# SignalReciever.net
KiCad netlist of a schematic drawn in Altium Designer
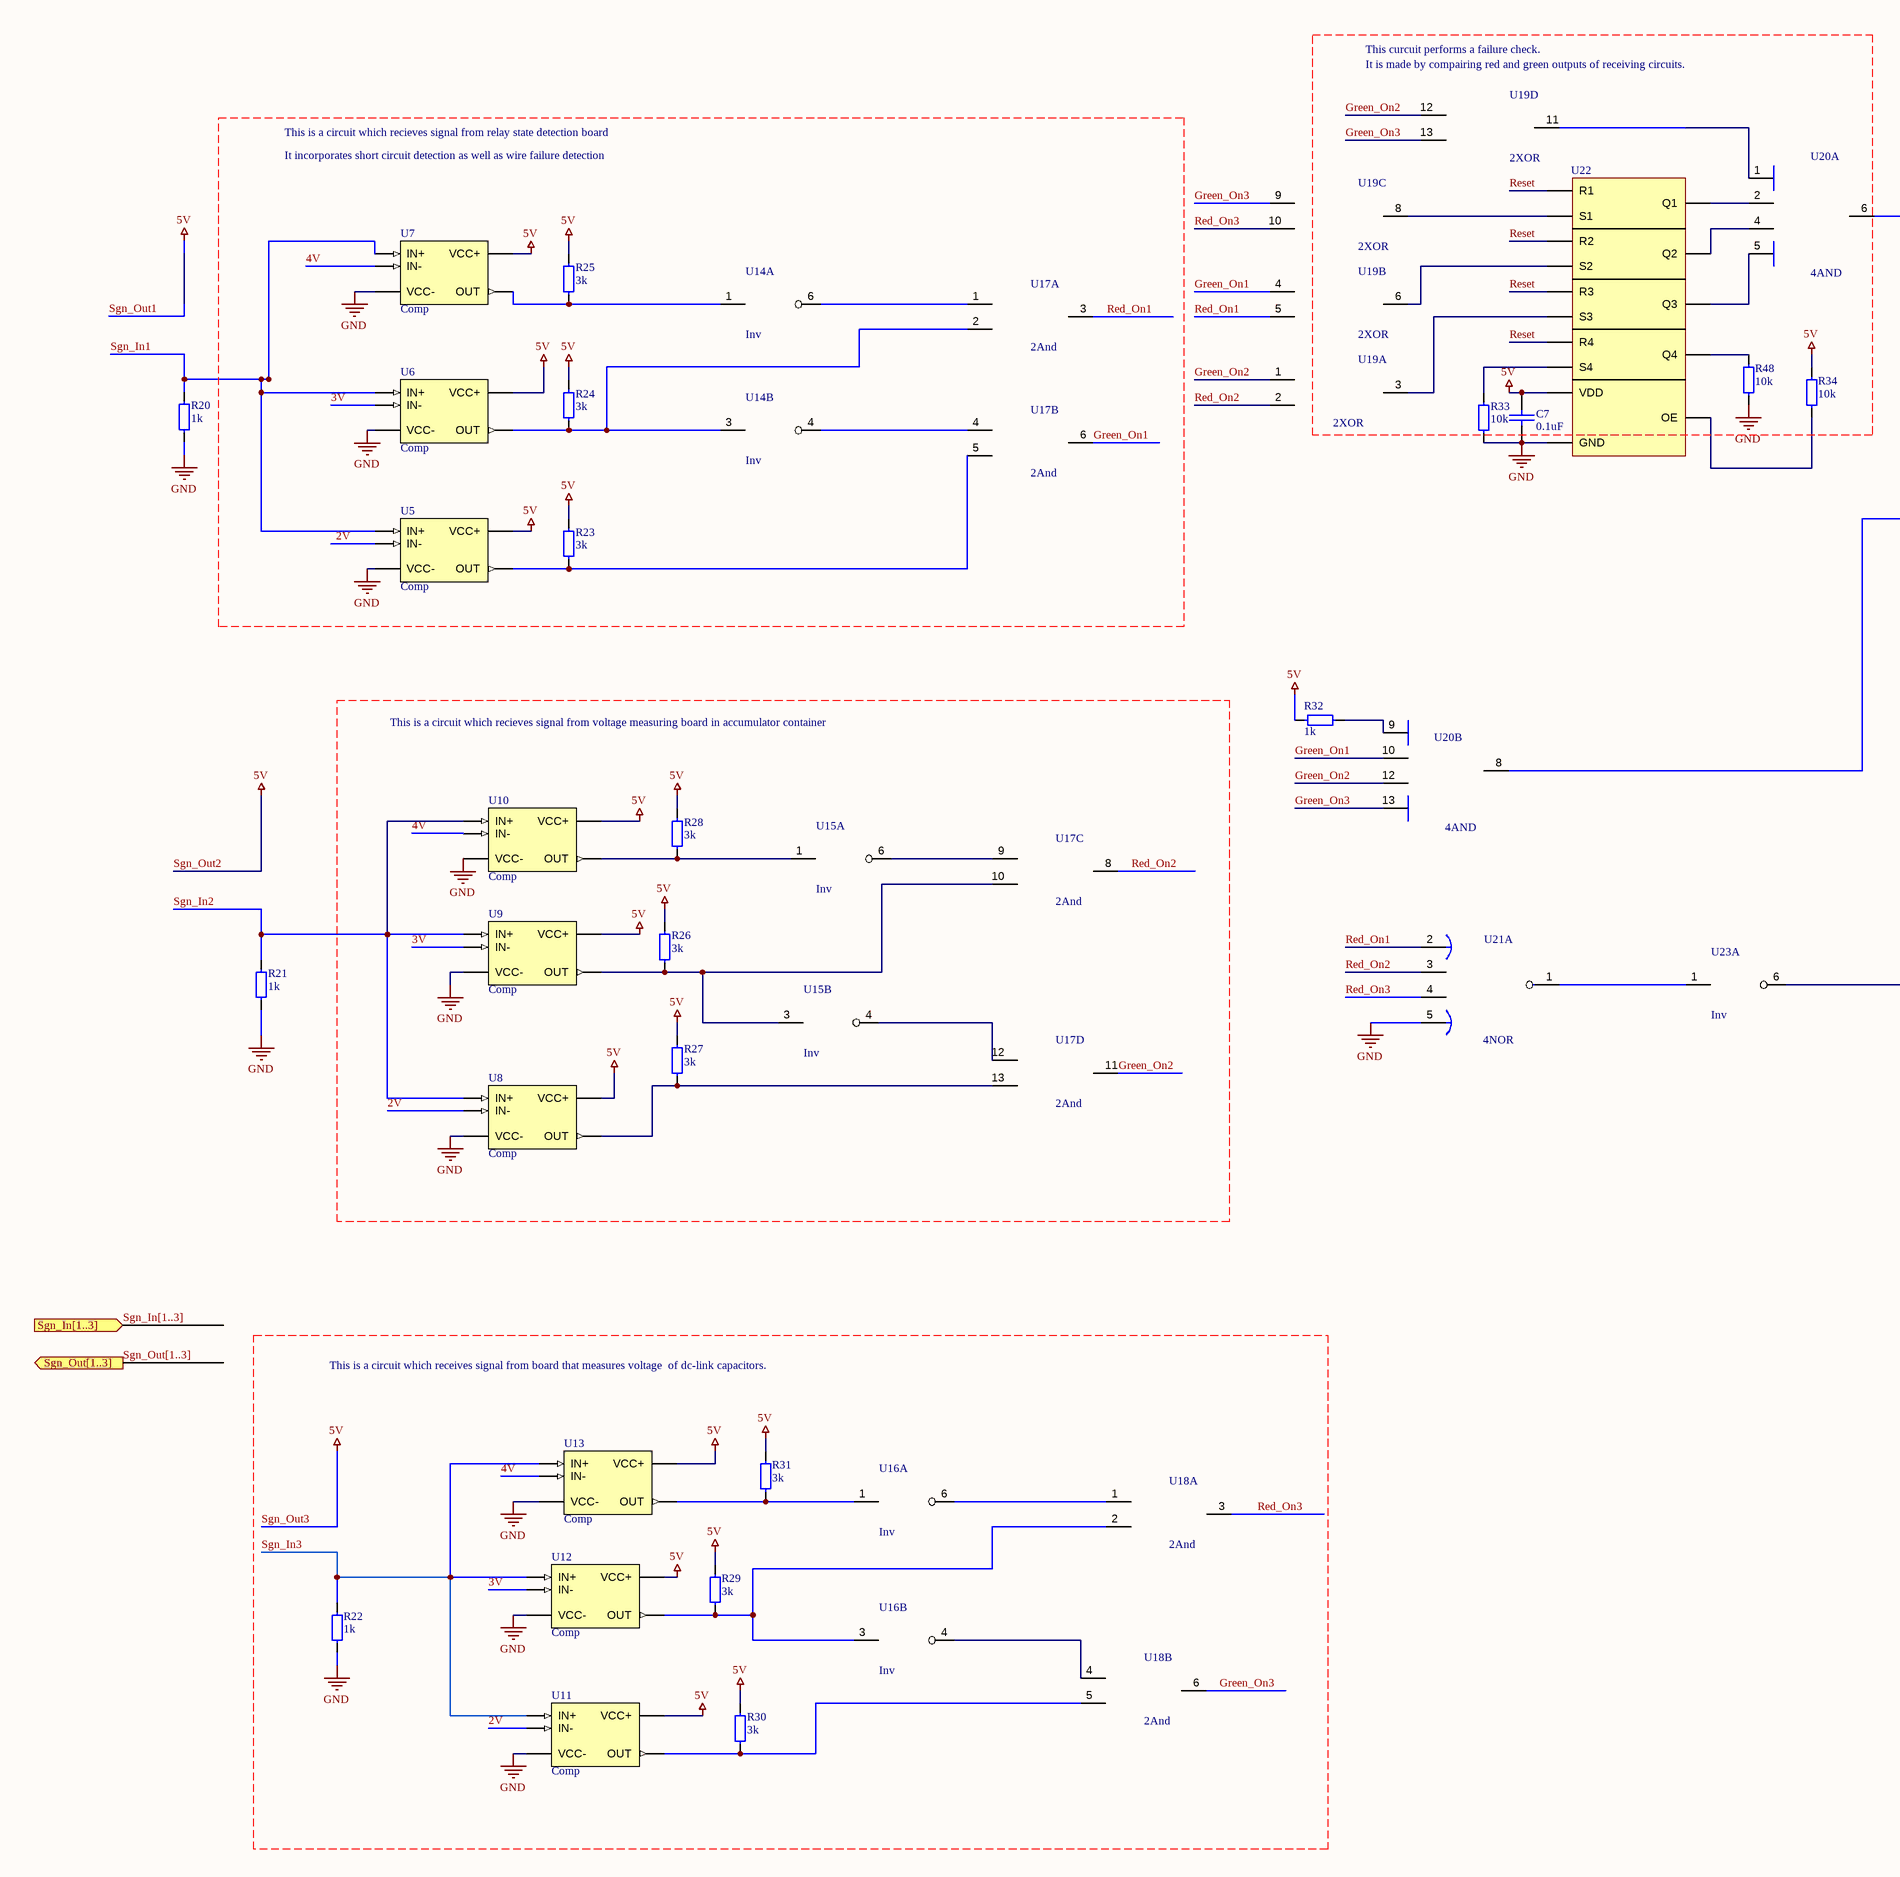
[diagram p0: SignalReciever.SchDoc, left]
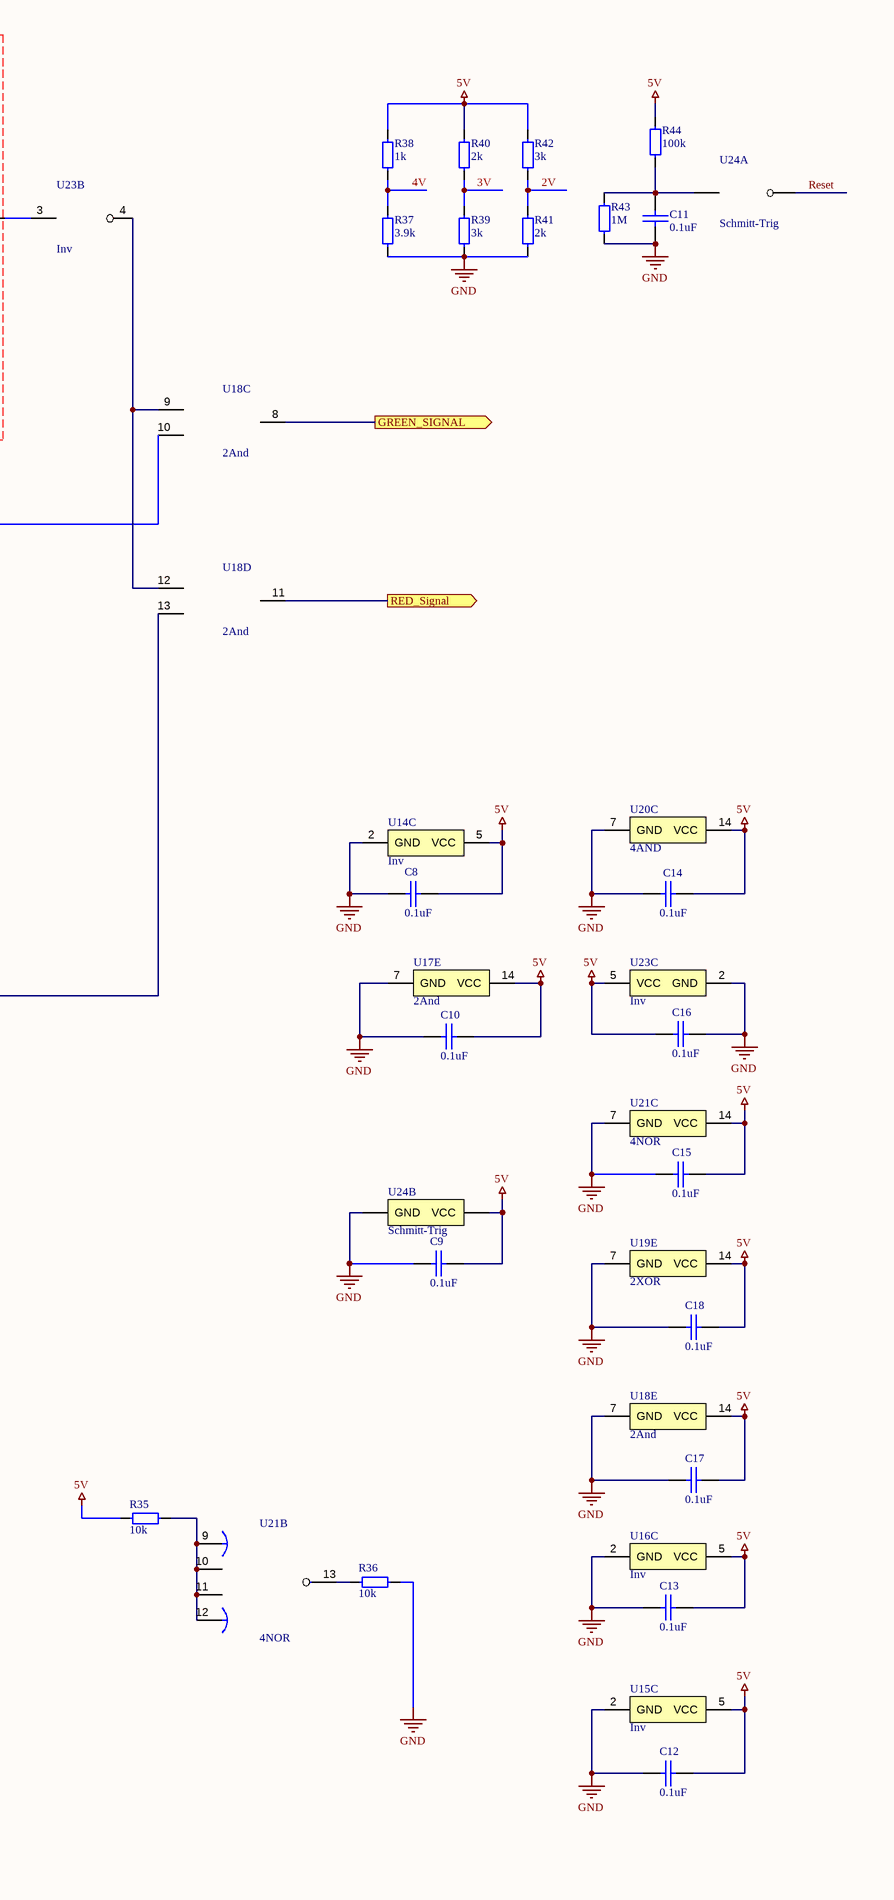
[diagram p1: SignalReciever.SchDoc, right]

(export (version "E")
  (design (tool "Eeschema 10.0.6"))
  (components
    (comp (ref "C7")
      (value "0.1uF")
      (footprint "0603 Capicator")
      (description "0.1uF X7R 16V 10% 0603")
      (fields
        (field (name "MANUFACTURER") "Murata Manufacturing")
        (field (name "PART NUMBER") "GRM188R71C104KA01D")
      )
      (libsource (lib "BRT_Components") (part "Cap 0.1uF (0603)"))
    )
    (comp (ref "C8")
      (value "0.1uF")
      (footprint "0603 Capicator")
      (description "0.1uF X7R 16V 10% 0603")
      (fields
        (field (name "MANUFACTURER") "Murata Manufacturing")
        (field (name "PART NUMBER") "GRM188R71C104KA01D")
      )
      (libsource (lib "BRT_Components") (part "Cap 0.1uF (0603)"))
    )
    (comp (ref "C9")
      (value "0.1uF")
      (footprint "0603 Capicator")
      (description "0.1uF X7R 16V 10% 0603")
      (fields
        (field (name "MANUFACTURER") "Murata Manufacturing")
        (field (name "PART NUMBER") "GRM188R71C104KA01D")
      )
      (libsource (lib "BRT_Components") (part "Cap 0.1uF (0603)"))
    )
    (comp (ref "C10")
      (value "0.1uF")
      (footprint "0603 Capicator")
      (description "0.1uF X7R 16V 10% 0603")
      (fields
        (field (name "MANUFACTURER") "Murata Manufacturing")
        (field (name "PART NUMBER") "GRM188R71C104KA01D")
      )
      (libsource (lib "BRT_Components") (part "Cap 0.1uF (0603)"))
    )
    (comp (ref "C11")
      (value "0.1uF")
      (footprint "0603 Capicator")
      (description "0.1uF X7R 16V 10% 0603")
      (fields
        (field (name "MANUFACTURER") "Murata Manufacturing")
        (field (name "PART NUMBER") "GRM188R71C104KA01D")
      )
      (libsource (lib "BRT_Components") (part "Cap 0.1uF (0603)"))
    )
    (comp (ref "C12")
      (value "0.1uF")
      (footprint "0603 Capicator")
      (description "0.1uF X7R 16V 10% 0603")
      (fields
        (field (name "MANUFACTURER") "Murata Manufacturing")
        (field (name "PART NUMBER") "GRM188R71C104KA01D")
      )
      (libsource (lib "BRT_Components") (part "Cap 0.1uF (0603)"))
    )
    (comp (ref "C13")
      (value "0.1uF")
      (footprint "0603 Capicator")
      (description "0.1uF X7R 16V 10% 0603")
      (fields
        (field (name "MANUFACTURER") "Murata Manufacturing")
        (field (name "PART NUMBER") "GRM188R71C104KA01D")
      )
      (libsource (lib "BRT_Components") (part "Cap 0.1uF (0603)"))
    )
    (comp (ref "C14")
      (value "0.1uF")
      (footprint "0603 Capicator")
      (description "0.1uF X7R 16V 10% 0603")
      (fields
        (field (name "MANUFACTURER") "Murata Manufacturing")
        (field (name "PART NUMBER") "GRM188R71C104KA01D")
      )
      (libsource (lib "BRT_Components") (part "Cap 0.1uF (0603)"))
    )
    (comp (ref "C15")
      (value "0.1uF")
      (footprint "0603 Capicator")
      (description "0.1uF X7R 16V 10% 0603")
      (fields
        (field (name "MANUFACTURER") "Murata Manufacturing")
        (field (name "PART NUMBER") "GRM188R71C104KA01D")
      )
      (libsource (lib "BRT_Components") (part "Cap 0.1uF (0603)"))
    )
    (comp (ref "C16")
      (value "0.1uF")
      (footprint "0603 Capicator")
      (description "0.1uF X7R 16V 10% 0603")
      (fields
        (field (name "MANUFACTURER") "Murata Manufacturing")
        (field (name "PART NUMBER") "GRM188R71C104KA01D")
      )
      (libsource (lib "BRT_Components") (part "Cap 0.1uF (0603)"))
    )
    (comp (ref "C17")
      (value "0.1uF")
      (footprint "0603 Capicator")
      (description "0.1uF X7R 16V 10% 0603")
      (fields
        (field (name "MANUFACTURER") "Murata Manufacturing")
        (field (name "PART NUMBER") "GRM188R71C104KA01D")
      )
      (libsource (lib "BRT_Components") (part "Cap 0.1uF (0603)"))
    )
    (comp (ref "C18")
      (value "0.1uF")
      (footprint "0603 Capicator")
      (description "0.1uF X7R 16V 10% 0603")
      (fields
        (field (name "MANUFACTURER") "Murata Manufacturing")
        (field (name "PART NUMBER") "GRM188R71C104KA01D")
      )
      (libsource (lib "BRT_Components") (part "Cap 0.1uF (0603)"))
    )
    (comp (ref "R20")
      (value "1k")
      (footprint "0603 Resistor")
      (description "0.1W 0603 1k, 1%")
      (fields (field (name "PART NUMBER") "RC0603FR-071KL") (field (name "MANUFACTURER") "Taiwan"))
      (libsource (lib "BRT_Components") (part "Res 1k (0603)"))
    )
    (comp (ref "R21")
      (value "1k")
      (footprint "0603 Resistor")
      (description "0.1W 0603 1k, 1%")
      (fields (field (name "PART NUMBER") "RC0603FR-071KL") (field (name "MANUFACTURER") "Taiwan"))
      (libsource (lib "BRT_Components") (part "Res 1k (0603)"))
    )
    (comp (ref "R22")
      (value "1k")
      (footprint "0603 Resistor")
      (description "0.1W 0603 1k, 1%")
      (fields (field (name "PART NUMBER") "RC0603FR-071KL") (field (name "MANUFACTURER") "Taiwan"))
      (libsource (lib "BRT_Components") (part "Res 1k (0603)"))
    )
    (comp (ref "R23")
      (value "3k")
      (footprint "0603 Resistor")
      (description "0.1W 0603 3k, 1%")
      (fields (field (name "PART NUMBER") "RC0603FR-073KL") (field (name "MANUFACTURER") "Taiwan"))
      (libsource (lib "BRT_Components") (part "Res 3k (0603)"))
    )
    (comp (ref "R24")
      (value "3k")
      (footprint "0603 Resistor")
      (description "0.1W 0603 3k, 1%")
      (fields (field (name "PART NUMBER") "RC0603FR-073KL") (field (name "MANUFACTURER") "Taiwan"))
      (libsource (lib "BRT_Components") (part "Res 3k (0603)"))
    )
    (comp (ref "R25")
      (value "3k")
      (footprint "0603 Resistor")
      (description "0.1W 0603 3k, 1%")
      (fields (field (name "PART NUMBER") "RC0603FR-073KL") (field (name "MANUFACTURER") "Taiwan"))
      (libsource (lib "BRT_Components") (part "Res 3k (0603)"))
    )
    (comp (ref "R26")
      (value "3k")
      (footprint "0603 Resistor")
      (description "0.1W 0603 3k, 1%")
      (fields (field (name "PART NUMBER") "RC0603FR-073KL") (field (name "MANUFACTURER") "Taiwan"))
      (libsource (lib "BRT_Components") (part "Res 3k (0603)"))
    )
    (comp (ref "R27")
      (value "3k")
      (footprint "0603 Resistor")
      (description "0.1W 0603 3k, 1%")
      (fields (field (name "PART NUMBER") "RC0603FR-073KL") (field (name "MANUFACTURER") "Taiwan"))
      (libsource (lib "BRT_Components") (part "Res 3k (0603)"))
    )
    (comp (ref "R28")
      (value "3k")
      (footprint "0603 Resistor")
      (description "0.1W 0603 3k, 1%")
      (fields (field (name "PART NUMBER") "RC0603FR-073KL") (field (name "MANUFACTURER") "Taiwan"))
      (libsource (lib "BRT_Components") (part "Res 3k (0603)"))
    )
    (comp (ref "R29")
      (value "3k")
      (footprint "0603 Resistor")
      (description "0.1W 0603 3k, 1%")
      (fields (field (name "PART NUMBER") "RC0603FR-073KL") (field (name "MANUFACTURER") "Taiwan"))
      (libsource (lib "BRT_Components") (part "Res 3k (0603)"))
    )
    (comp (ref "R30")
      (value "3k")
      (footprint "0603 Resistor")
      (description "0.1W 0603 3k, 1%")
      (fields (field (name "PART NUMBER") "RC0603FR-073KL") (field (name "MANUFACTURER") "Taiwan"))
      (libsource (lib "BRT_Components") (part "Res 3k (0603)"))
    )
    (comp (ref "R31")
      (value "3k")
      (footprint "0603 Resistor")
      (description "0.1W 0603 3k, 1%")
      (fields (field (name "PART NUMBER") "RC0603FR-073KL") (field (name "MANUFACTURER") "Taiwan"))
      (libsource (lib "BRT_Components") (part "Res 3k (0603)"))
    )
    (comp (ref "R32")
      (value "1k")
      (footprint "0603 Resistor")
      (description "0.1W 0603 1k, 1%")
      (fields (field (name "PART NUMBER") "RC0603FR-071KL") (field (name "MANUFACTURER") "Taiwan"))
      (libsource (lib "BRT_Components") (part "Res 1k (0603)"))
    )
    (comp (ref "R33")
      (value "10k")
      (footprint "0603 Resistor")
      (description "0.1W 0603 10k, 1%")
      (fields (field (name "PART NUMBER") "RC0603FR-0710KL") (field (name "MANUFACTURER") "Taiwan"))
      (libsource (lib "BRT_Components") (part "Res 10k (0603)"))
    )
    (comp (ref "R34")
      (value "10k")
      (footprint "0603 Resistor")
      (description "0.1W 0603 10k, 1%")
      (fields (field (name "PART NUMBER") "RC0603FR-0710KL") (field (name "MANUFACTURER") "Taiwan"))
      (libsource (lib "BRT_Components") (part "Res 10k (0603)"))
    )
    (comp (ref "R35")
      (value "10k")
      (footprint "0603 Resistor")
      (description "0.1W 0603 10k, 1%")
      (fields (field (name "PART NUMBER") "RC0603FR-0710KL") (field (name "MANUFACTURER") "Taiwan"))
      (libsource (lib "BRT_Components") (part "Res 10k (0603)"))
    )
    (comp (ref "R36")
      (value "10k")
      (footprint "0603 Resistor")
      (description "0.1W 0603 10k, 1%")
      (fields (field (name "PART NUMBER") "RC0603FR-0710KL") (field (name "MANUFACTURER") "Taiwan"))
      (libsource (lib "BRT_Components") (part "Res 10k (0603)"))
    )
    (comp (ref "R37")
      (value "3.9k")
      (footprint "0603 Resistor")
      (description "0.1W 0603 3.9k, 1%")
      (fields (field (name "PART NUMBER") "RC0603FR-073K9L") (field (name "MANUFACTURER") "Taiwan"))
      (libsource (lib "BRT_Components") (part "Res 3.9k (0603)"))
    )
    (comp (ref "R38")
      (value "1k")
      (footprint "0603 Resistor")
      (description "0.1W 0603 1k, 1%")
      (fields (field (name "PART NUMBER") "RC0603FR-071KL") (field (name "MANUFACTURER") "Taiwan"))
      (libsource (lib "BRT_Components") (part "Res 1k (0603)"))
    )
    (comp (ref "R39")
      (value "3k")
      (footprint "0603 Resistor")
      (description "0.1W 0603 3k, 1%")
      (fields (field (name "PART NUMBER") "RC0603FR-073KL") (field (name "MANUFACTURER") "Taiwan"))
      (libsource (lib "BRT_Components") (part "Res 3k (0603)"))
    )
    (comp (ref "R40")
      (value "2k")
      (footprint "0603 Resistor")
      (description "0.1W 0603 2k, 1%")
      (fields (field (name "PART NUMBER") "RC0603FR-072KL") (field (name "MANUFACTURER") "Taiwan"))
      (libsource (lib "BRT_Components") (part "Res 2k (0603)"))
    )
    (comp (ref "R41")
      (value "2k")
      (footprint "0603 Resistor")
      (description "0.1W 0603 2k, 1%")
      (fields (field (name "PART NUMBER") "RC0603FR-072KL") (field (name "MANUFACTURER") "Taiwan"))
      (libsource (lib "BRT_Components") (part "Res 2k (0603)"))
    )
    (comp (ref "R42")
      (value "3k")
      (footprint "0603 Resistor")
      (description "0.1W 0603 3k, 1%")
      (fields (field (name "PART NUMBER") "RC0603FR-073KL") (field (name "MANUFACTURER") "Taiwan"))
      (libsource (lib "BRT_Components") (part "Res 3k (0603)"))
    )
    (comp (ref "R43")
      (value "1M")
      (footprint "0603 Resistor")
      (description "0.1W 0603 1M, 1%")
      (fields (field (name "PART NUMBER") "RC0603FR-071ML") (field (name "MANUFACTURER") "Taiwan"))
      (libsource (lib "BRT_Components") (part "Res 1M (0603)"))
    )
    (comp (ref "R44")
      (value "100k")
      (footprint "0603 Resistor")
      (description "0.1W 0603 100k, 1%")
      (fields (field (name "PART NUMBER") "RC0603FR-07100KL") (field (name "MANUFACTURER") "Taiwan"))
      (libsource (lib "BRT_Components") (part "Res 100k (0603)"))
    )
    (comp (ref "R48")
      (value "10k")
      (footprint "0603 Resistor")
      (description "0.1W 0603 10k, 1%")
      (fields (field (name "PART NUMBER") "RC0603FR-0710KL") (field (name "MANUFACTURER") "Taiwan"))
      (libsource (lib "BRT_Components") (part "Res 10k (0603)"))
    )
    (comp (ref "U5")
      (value "Comp")
      (footprint "SOT-23-5")
      (description "Differential comparator with strobes")
      (fields (field (name "PART NUMBER") "LMV331M5/NOPB") (field (name "MANUFACTURER") "Texas Instruments"))
      (libsource (lib "BRT_Components") (part "Comparator [LMV]"))
    )
    (comp (ref "U6")
      (value "Comp")
      (footprint "SOT-23-5")
      (description "Differential comparator with strobes")
      (fields (field (name "PART NUMBER") "LMV331M5/NOPB") (field (name "MANUFACTURER") "Texas Instruments"))
      (libsource (lib "BRT_Components") (part "Comparator [LMV]"))
    )
    (comp (ref "U7")
      (value "Comp")
      (footprint "SOT-23-5")
      (description "Differential comparator with strobes")
      (fields (field (name "PART NUMBER") "LMV331M5/NOPB") (field (name "MANUFACTURER") "Texas Instruments"))
      (libsource (lib "BRT_Components") (part "Comparator [LMV]"))
    )
    (comp (ref "U8")
      (value "Comp")
      (footprint "SOT-23-5")
      (description "Differential comparator with strobes")
      (fields (field (name "PART NUMBER") "LMV331M5/NOPB") (field (name "MANUFACTURER") "Texas Instruments"))
      (libsource (lib "BRT_Components") (part "Comparator [LMV]"))
    )
    (comp (ref "U9")
      (value "Comp")
      (footprint "SOT-23-5")
      (description "Differential comparator with strobes")
      (fields (field (name "PART NUMBER") "LMV331M5/NOPB") (field (name "MANUFACTURER") "Texas Instruments"))
      (libsource (lib "BRT_Components") (part "Comparator [LMV]"))
    )
    (comp (ref "U10")
      (value "Comp")
      (footprint "SOT-23-5")
      (description "Differential comparator with strobes")
      (fields (field (name "PART NUMBER") "LMV331M5/NOPB") (field (name "MANUFACTURER") "Texas Instruments"))
      (libsource (lib "BRT_Components") (part "Comparator [LMV]"))
    )
    (comp (ref "U11")
      (value "Comp")
      (footprint "SOT-23-5")
      (description "Differential comparator with strobes")
      (fields (field (name "PART NUMBER") "LMV331M5/NOPB") (field (name "MANUFACTURER") "Texas Instruments"))
      (libsource (lib "BRT_Components") (part "Comparator [LMV]"))
    )
    (comp (ref "U12")
      (value "Comp")
      (footprint "SOT-23-5")
      (description "Differential comparator with strobes")
      (fields (field (name "PART NUMBER") "LMV331M5/NOPB") (field (name "MANUFACTURER") "Texas Instruments"))
      (libsource (lib "BRT_Components") (part "Comparator [LMV]"))
    )
    (comp (ref "U13")
      (value "Comp")
      (footprint "SOT-23-5")
      (description "Differential comparator with strobes")
      (fields (field (name "PART NUMBER") "LMV331M5/NOPB") (field (name "MANUFACTURER") "Texas Instruments"))
      (libsource (lib "BRT_Components") (part "Comparator [LMV]"))
    )
    (comp (ref "U14")
      (value "Inv")
      (footprint "SOT236")
      (description "Dual inverter, 1.65-5.5V")
      (fields
        (field (name "MANUFACTURER") "Texas Instruments")
        (field (name "PART NUMBER") "SN74LVC2G04DBVR")
      )
      (libsource (lib "") (part "Inverter (SN74)_1"))
    )
    (comp (ref "U15")
      (value "Inv")
      (footprint "SOT236")
      (description "Dual inverter, 1.65-5.5V")
      (fields
        (field (name "MANUFACTURER") "Texas Instruments")
        (field (name "PART NUMBER") "SN74LVC2G04DBVR")
      )
      (libsource (lib "") (part "Inverter (SN74)_1"))
    )
    (comp (ref "U16")
      (value "Inv")
      (footprint "SOT236")
      (description "Dual inverter, 1.65-5.5V")
      (fields
        (field (name "MANUFACTURER") "Texas Instruments")
        (field (name "PART NUMBER") "SN74LVC2G04DBVR")
      )
      (libsource (lib "BRT_Components") (part "Inverter (SN74)"))
    )
    (comp (ref "U17")
      (value "2And")
      (footprint "SOIC-14")
      (description "4 logic elements \"2AND\"")
      (fields (field (name "PART NUMBER") "SN74AC08DR") (field (name "MANUFACTURER") "Texas Instruments"))
      (libsource (lib "BRT_Components") (part "4(2And)"))
    )
    (comp (ref "U18")
      (value "2And")
      (footprint "SOIC-14")
      (description "4 logic elements \"2AND\"")
      (fields (field (name "PART NUMBER") "SN74AC08DR") (field (name "MANUFACTURER") "Texas Instruments"))
      (libsource (lib "BRT_Components") (part "4(2And)"))
    )
    (comp (ref "U19")
      (value "2XOR")
      (footprint "SOIC-14")
      (description "4 logic elements \"2XOR\"")
      (fields (field (name "PART NUMBER") "74HC86D,653") (field (name "MANUFACTURER") "Nexperia"))
      (libsource (lib "BRT_Components") (part "4(2XOR)"))
    )
    (comp (ref "U20")
      (value "4AND")
      (footprint "SOIC-14")
      (description "2 logic elements \"4AND\"")
      (fields (field (name "PART NUMBER") "74HC21D,653") (field (name "MANUFACTURER") "Nexperia"))
      (libsource (lib "BRT_Components") (part "2(4AND)"))
    )
    (comp (ref "U21")
      (value "4NOR")
      (footprint "SOIC-14")
      (description "2 logic elements \"4NOR\"")
      (fields (field (name "PART NUMBER") "74HC4002D,652") (field (name "MANUFACTURER") "Nexperia"))
      (libsource (lib "BRT_Components") (part "2(4NOR)"))
    )
    (comp (ref "U22")
      (value "quad R/S latch with 3-state outputs")
      (footprint "SOIC-16")
      (description "The HEF4043B is a quad R/S latch with 3-state outputs and common output enable input (OE).")
      (libsource (lib "BRT_Components") (part "4 RS triggers"))
    )
    (comp (ref "U23")
      (value "Inv")
      (footprint "SOT236")
      (description "Dual inverter, 1.65-5.5V")
      (fields
        (field (name "MANUFACTURER") "Texas Instruments")
        (field (name "PART NUMBER") "SN74LVC2G04DBVR")
      )
      (libsource (lib "BRT_Components") (part "Inverter (SN74)"))
    )
    (comp (ref "U24")
      (value "Schmitt-Trig")
      (footprint "SOT-23-5")
      (fields (field (name "PART NUMBER") "NC7SZ14M5X") (field (name "MANUFACTURER") "ON Semiconductor"))
      (libsource (lib "BRT_Components") (part "Schmitt Trigger [NC7SZ]"))
    )
  )
  (nets
    (net (code "1") (name "/2V") (class "Default")
      (node (ref "R41") (pin "2") (pinfunction "2_2") (pintype "passive"))
      (node (ref "R42") (pin "1") (pinfunction "1_1") (pintype "passive"))
      (node (ref "U11") (pin "3") (pinfunction "IN-_3") (pintype "input"))
      (node (ref "U5") (pin "3") (pinfunction "IN-_3") (pintype "input"))
      (node (ref "U8") (pin "3") (pinfunction "IN-_3") (pintype "input"))
    )
    (net (code "2") (name "/3V") (class "Default")
      (node (ref "R39") (pin "2") (pinfunction "2_2") (pintype "passive"))
      (node (ref "R40") (pin "1") (pinfunction "1_1") (pintype "passive"))
      (node (ref "U12") (pin "3") (pinfunction "IN-_3") (pintype "input"))
      (node (ref "U6") (pin "3") (pinfunction "IN-_3") (pintype "input"))
      (node (ref "U9") (pin "3") (pinfunction "IN-_3") (pintype "input"))
    )
    (net (code "3") (name "/4V") (class "Default")
      (node (ref "R37") (pin "2") (pinfunction "2_2") (pintype "passive"))
      (node (ref "R38") (pin "2") (pinfunction "2_2") (pintype "passive"))
      (node (ref "U10") (pin "3") (pinfunction "IN-_3") (pintype "input"))
      (node (ref "U13") (pin "3") (pinfunction "IN-_3") (pintype "input"))
      (node (ref "U7") (pin "3") (pinfunction "IN-_3") (pintype "input"))
    )
    (net (code "4") (name "/GREEN_SIGNAL") (class "Default")
      (node (ref "U18") (pin "8") (pinfunction "3Y_8") (pintype "passive"))
    )
    (net (code "5") (name "/Green_On1") (class "Default")
      (node (ref "U17") (pin "6") (pinfunction "2Y_6") (pintype "passive"))
      (node (ref "U19") (pin "4") (pinfunction "A_4") (pintype "passive"))
      (node (ref "U20") (pin "10") (pinfunction "B_10") (pintype "passive"))
    )
    (net (code "6") (name "/Green_On2") (class "Default")
      (node (ref "U17") (pin "11") (pinfunction "4Y_11") (pintype "passive"))
      (node (ref "U19") (pin "1") (pinfunction "A_1") (pintype "passive"))
      (node (ref "U19") (pin "12") (pinfunction "A_12") (pintype "passive"))
      (node (ref "U20") (pin "12") (pinfunction "C_12") (pintype "passive"))
    )
    (net (code "7") (name "/Green_On3") (class "Default")
      (node (ref "U18") (pin "6") (pinfunction "2Y_6") (pintype "passive"))
      (node (ref "U19") (pin "13") (pinfunction "B_13") (pintype "passive"))
      (node (ref "U19") (pin "9") (pinfunction "A_9") (pintype "passive"))
      (node (ref "U20") (pin "13") (pinfunction "D_13") (pintype "passive"))
    )
    (net (code "8") (name "/RED_Signal") (class "Default")
      (node (ref "U18") (pin "11") (pinfunction "4Y_11") (pintype "passive"))
    )
    (net (code "9") (name "/Red_On1") (class "Default")
      (node (ref "U17") (pin "3") (pinfunction "1Y_3") (pintype "passive"))
      (node (ref "U19") (pin "5") (pinfunction "B_5") (pintype "passive"))
      (node (ref "U21") (pin "2") (pinfunction "A_2") (pintype "passive"))
    )
    (net (code "10") (name "/Red_On2") (class "Default")
      (node (ref "U17") (pin "8") (pinfunction "3Y_8") (pintype "passive"))
      (node (ref "U19") (pin "2") (pinfunction "B_2") (pintype "passive"))
      (node (ref "U21") (pin "3") (pinfunction "B_3") (pintype "passive"))
    )
    (net (code "11") (name "/Red_On3") (class "Default")
      (node (ref "U18") (pin "3") (pinfunction "1Y_3") (pintype "passive"))
      (node (ref "U19") (pin "10") (pinfunction "B_10") (pintype "passive"))
      (node (ref "U21") (pin "4") (pinfunction "C_4") (pintype "passive"))
    )
    (net (code "12") (name "/Reset") (class "Default")
      (node (ref "U22") (pin "11") (pinfunction "R3_11") (pintype "passive"))
      (node (ref "U22") (pin "15") (pinfunction "R4_15") (pintype "passive"))
      (node (ref "U22") (pin "3") (pinfunction "R1_3") (pintype "passive"))
      (node (ref "U22") (pin "7") (pinfunction "R2_7") (pintype "passive"))
      (node (ref "U24") (pin "4") (pinfunction "Y_4") (pintype "passive"))
    )
    (net (code "13") (name "/Sgn_In1") (class "Default")
      (node (ref "R20") (pin "2") (pinfunction "2_2") (pintype "passive"))
      (node (ref "U5") (pin "1") (pinfunction "IN+_1") (pintype "input"))
      (node (ref "U6") (pin "1") (pinfunction "IN+_1") (pintype "input"))
      (node (ref "U7") (pin "1") (pinfunction "IN+_1") (pintype "input"))
    )
    (net (code "14") (name "/Sgn_In2") (class "Default")
      (node (ref "R21") (pin "2") (pinfunction "2_2") (pintype "passive"))
      (node (ref "U10") (pin "1") (pinfunction "IN+_1") (pintype "input"))
      (node (ref "U8") (pin "1") (pinfunction "IN+_1") (pintype "input"))
      (node (ref "U9") (pin "1") (pinfunction "IN+_1") (pintype "input"))
    )
    (net (code "15") (name "/Sgn_In3") (class "Default")
      (node (ref "R22") (pin "2") (pinfunction "2_2") (pintype "passive"))
      (node (ref "U11") (pin "1") (pinfunction "IN+_1") (pintype "input"))
      (node (ref "U12") (pin "1") (pinfunction "IN+_1") (pintype "input"))
      (node (ref "U13") (pin "1") (pinfunction "IN+_1") (pintype "input"))
    )
    (net (code "18") (name "5V") (class "Default")
      (node (ref "C10") (pin "2") (pinfunction "2_2") (pintype "passive"))
      (node (ref "C12") (pin "2") (pinfunction "2_2") (pintype "passive"))
      (node (ref "C13") (pin "2") (pinfunction "2_2") (pintype "passive"))
      (node (ref "C14") (pin "2") (pinfunction "2_2") (pintype "passive"))
      (node (ref "C15") (pin "2") (pinfunction "2_2") (pintype "passive"))
      (node (ref "C16") (pin "1") (pinfunction "1_1") (pintype "passive"))
      (node (ref "C17") (pin "2") (pinfunction "2_2") (pintype "passive"))
      (node (ref "C18") (pin "2") (pinfunction "2_2") (pintype "passive"))
      (node (ref "C7") (pin "2") (pinfunction "2_2") (pintype "passive"))
      (node (ref "C8") (pin "2") (pinfunction "2_2") (pintype "passive"))
      (node (ref "C9") (pin "2") (pinfunction "2_2") (pintype "passive"))
      (node (ref "R23") (pin "2") (pinfunction "2_2") (pintype "passive"))
      (node (ref "R24") (pin "2") (pinfunction "2_2") (pintype "passive"))
      (node (ref "R25") (pin "2") (pinfunction "2_2") (pintype "passive"))
      (node (ref "R26") (pin "2") (pinfunction "2_2") (pintype "passive"))
      (node (ref "R27") (pin "2") (pinfunction "2_2") (pintype "passive"))
      (node (ref "R28") (pin "2") (pinfunction "2_2") (pintype "passive"))
      (node (ref "R29") (pin "2") (pinfunction "2_2") (pintype "passive"))
      (node (ref "R30") (pin "2") (pinfunction "2_2") (pintype "passive"))
      (node (ref "R31") (pin "2") (pinfunction "2_2") (pintype "passive"))
      (node (ref "R32") (pin "2") (pinfunction "2_2") (pintype "passive"))
      (node (ref "R34") (pin "1") (pinfunction "1_1") (pintype "passive"))
      (node (ref "R35") (pin "1") (pinfunction "1_1") (pintype "passive"))
      (node (ref "R38") (pin "1") (pinfunction "1_1") (pintype "passive"))
      (node (ref "R40") (pin "2") (pinfunction "2_2") (pintype "passive"))
      (node (ref "R42") (pin "2") (pinfunction "2_2") (pintype "passive"))
      (node (ref "R44") (pin "2") (pinfunction "2_2") (pintype "passive"))
      (node (ref "U10") (pin "5") (pinfunction "VCC+_5") (pintype "power_in"))
      (node (ref "U11") (pin "5") (pinfunction "VCC+_5") (pintype "power_in"))
      (node (ref "U12") (pin "5") (pinfunction "VCC+_5") (pintype "power_in"))
      (node (ref "U13") (pin "5") (pinfunction "VCC+_5") (pintype "power_in"))
      (node (ref "U14") (pin "5") (pinfunction "VCC_5") (pintype "power_in"))
      (node (ref "U15") (pin "5") (pinfunction "VCC_5") (pintype "power_in"))
      (node (ref "U16") (pin "5") (pinfunction "VCC_5") (pintype "power_in"))
      (node (ref "U17") (pin "14") (pinfunction "VCC_14") (pintype "power_in"))
      (node (ref "U18") (pin "14") (pinfunction "VCC_14") (pintype "power_in"))
      (node (ref "U19") (pin "14") (pinfunction "VCC_14") (pintype "passive"))
      (node (ref "U20") (pin "14") (pinfunction "VCC_14") (pintype "passive"))
      (node (ref "U21") (pin "14") (pinfunction "VCC_14") (pintype "passive"))
      (node (ref "U22") (pin "8") (pinfunction "VDD_8") (pintype "passive"))
      (node (ref "U23") (pin "5") (pinfunction "VCC_5") (pintype "power_in"))
      (node (ref "U24") (pin "5") (pinfunction "VCC_5") (pintype "power_in"))
      (node (ref "U5") (pin "5") (pinfunction "VCC+_5") (pintype "power_in"))
      (node (ref "U6") (pin "5") (pinfunction "VCC+_5") (pintype "power_in"))
      (node (ref "U7") (pin "5") (pinfunction "VCC+_5") (pintype "power_in"))
      (node (ref "U8") (pin "5") (pinfunction "VCC+_5") (pintype "power_in"))
      (node (ref "U9") (pin "5") (pinfunction "VCC+_5") (pintype "power_in"))
    )
    (net (code "19") (name "GND") (class "Default")
      (node (ref "C10") (pin "1") (pinfunction "1_1") (pintype "passive"))
      (node (ref "C11") (pin "1") (pinfunction "1_1") (pintype "passive"))
      (node (ref "C12") (pin "1") (pinfunction "1_1") (pintype "passive"))
      (node (ref "C13") (pin "1") (pinfunction "1_1") (pintype "passive"))
      (node (ref "C14") (pin "1") (pinfunction "1_1") (pintype "passive"))
      (node (ref "C15") (pin "1") (pinfunction "1_1") (pintype "passive"))
      (node (ref "C16") (pin "2") (pinfunction "2_2") (pintype "passive"))
      (node (ref "C17") (pin "1") (pinfunction "1_1") (pintype "passive"))
      (node (ref "C18") (pin "1") (pinfunction "1_1") (pintype "passive"))
      (node (ref "C7") (pin "1") (pinfunction "1_1") (pintype "passive"))
      (node (ref "C8") (pin "1") (pinfunction "1_1") (pintype "passive"))
      (node (ref "C9") (pin "1") (pinfunction "1_1") (pintype "passive"))
      (node (ref "R20") (pin "1") (pinfunction "1_1") (pintype "passive"))
      (node (ref "R21") (pin "1") (pinfunction "1_1") (pintype "passive"))
      (node (ref "R22") (pin "1") (pinfunction "1_1") (pintype "passive"))
      (node (ref "R33") (pin "2") (pinfunction "2_2") (pintype "passive"))
      (node (ref "R36") (pin "2") (pinfunction "2_2") (pintype "passive"))
      (node (ref "R37") (pin "1") (pinfunction "1_1") (pintype "passive"))
      (node (ref "R39") (pin "1") (pinfunction "1_1") (pintype "passive"))
      (node (ref "R41") (pin "1") (pinfunction "1_1") (pintype "passive"))
      (node (ref "R43") (pin "1") (pinfunction "1_1") (pintype "passive"))
      (node (ref "R48") (pin "2") (pinfunction "2_2") (pintype "passive"))
      (node (ref "U10") (pin "2") (pinfunction "VCC-_2") (pintype "power_in"))
      (node (ref "U11") (pin "2") (pinfunction "VCC-_2") (pintype "power_in"))
      (node (ref "U12") (pin "2") (pinfunction "VCC-_2") (pintype "power_in"))
      (node (ref "U13") (pin "2") (pinfunction "VCC-_2") (pintype "power_in"))
      (node (ref "U14") (pin "2") (pinfunction "GND_2") (pintype "power_in"))
      (node (ref "U15") (pin "2") (pinfunction "GND_2") (pintype "power_in"))
      (node (ref "U16") (pin "2") (pinfunction "GND_2") (pintype "power_in"))
      (node (ref "U17") (pin "7") (pinfunction "GND_7") (pintype "power_in"))
      (node (ref "U18") (pin "7") (pinfunction "GND_7") (pintype "power_in"))
      (node (ref "U19") (pin "7") (pinfunction "GND_7") (pintype "passive"))
      (node (ref "U20") (pin "7") (pinfunction "GND_7") (pintype "passive"))
      (node (ref "U21") (pin "5") (pinfunction "D_5") (pintype "passive"))
      (node (ref "U21") (pin "7") (pinfunction "GND_7") (pintype "passive"))
      (node (ref "U22") (pin "16") (pinfunction "GND_16") (pintype "passive"))
      (node (ref "U23") (pin "2") (pinfunction "GND_2") (pintype "power_in"))
      (node (ref "U24") (pin "3") (pinfunction "GND_3") (pintype "power_in"))
      (node (ref "U5") (pin "2") (pinfunction "VCC-_2") (pintype "power_in"))
      (node (ref "U6") (pin "2") (pinfunction "VCC-_2") (pintype "power_in"))
      (node (ref "U7") (pin "2") (pinfunction "VCC-_2") (pintype "power_in"))
      (node (ref "U8") (pin "2") (pinfunction "VCC-_2") (pintype "power_in"))
      (node (ref "U9") (pin "2") (pinfunction "VCC-_2") (pintype "power_in"))
    )
    (net (code "20") (name "Net-(U10-OUT)") (class "Default")
      (node (ref "R28") (pin "1") (pinfunction "1_1") (pintype "passive"))
      (node (ref "U10") (pin "4") (pinfunction "OUT_4") (pintype "output"))
      (node (ref "U15") (pin "1") (pinfunction "1A_1") (pintype "passive"))
    )
    (net (code "21") (name "Net-(U11-OUT)") (class "Default")
      (node (ref "R30") (pin "1") (pinfunction "1_1") (pintype "passive"))
      (node (ref "U11") (pin "4") (pinfunction "OUT_4") (pintype "output"))
      (node (ref "U18") (pin "5") (pinfunction "2B_5") (pintype "passive"))
    )
    (net (code "22") (name "Net-(U12-OUT)") (class "Default")
      (node (ref "R29") (pin "1") (pinfunction "1_1") (pintype "passive"))
      (node (ref "U12") (pin "4") (pinfunction "OUT_4") (pintype "output"))
      (node (ref "U16") (pin "3") (pinfunction "2А_3") (pintype "passive"))
      (node (ref "U18") (pin "2") (pinfunction "1B_2") (pintype "passive"))
    )
    (net (code "23") (name "Net-(U13-OUT)") (class "Default")
      (node (ref "R31") (pin "1") (pinfunction "1_1") (pintype "passive"))
      (node (ref "U13") (pin "4") (pinfunction "OUT_4") (pintype "output"))
      (node (ref "U16") (pin "1") (pinfunction "1A_1") (pintype "passive"))
    )
    (net (code "24") (name "Net-(U14A-1A)") (class "Default")
      (node (ref "R25") (pin "1") (pinfunction "1_1") (pintype "passive"))
      (node (ref "U14") (pin "1") (pinfunction "1A_1") (pintype "passive"))
      (node (ref "U7") (pin "4") (pinfunction "OUT_4") (pintype "output"))
    )
    (net (code "25") (name "Net-(U14A-1Y)") (class "Default")
      (node (ref "U14") (pin "6") (pinfunction "1Y_6") (pintype "passive"))
      (node (ref "U17") (pin "1") (pinfunction "1A_1") (pintype "passive"))
    )
    (net (code "26") (name "Net-(U14B-2Y)") (class "Default")
      (node (ref "U14") (pin "4") (pinfunction "2Y_4") (pintype "passive"))
      (node (ref "U17") (pin "4") (pinfunction "2A_4") (pintype "passive"))
    )
    (net (code "27") (name "Net-(U14B-2А)") (class "Default")
      (node (ref "R24") (pin "1") (pinfunction "1_1") (pintype "passive"))
      (node (ref "U14") (pin "3") (pinfunction "2А_3") (pintype "passive"))
      (node (ref "U17") (pin "2") (pinfunction "1B_2") (pintype "passive"))
      (node (ref "U6") (pin "4") (pinfunction "OUT_4") (pintype "output"))
    )
    (net (code "28") (name "Net-(U15A-1Y)") (class "Default")
      (node (ref "U15") (pin "6") (pinfunction "1Y_6") (pintype "passive"))
      (node (ref "U17") (pin "9") (pinfunction "3A_9") (pintype "passive"))
    )
    (net (code "29") (name "Net-(U15B-2Y)") (class "Default")
      (node (ref "U15") (pin "4") (pinfunction "2Y_4") (pintype "passive"))
      (node (ref "U17") (pin "12") (pinfunction "4A_12") (pintype "passive"))
    )
    (net (code "30") (name "Net-(U15B-2А)") (class "Default")
      (node (ref "R26") (pin "1") (pinfunction "1_1") (pintype "passive"))
      (node (ref "U15") (pin "3") (pinfunction "2А_3") (pintype "passive"))
      (node (ref "U17") (pin "10") (pinfunction "3B_10") (pintype "passive"))
      (node (ref "U9") (pin "4") (pinfunction "OUT_4") (pintype "output"))
    )
    (net (code "31") (name "Net-(U16A-1Y)") (class "Default")
      (node (ref "U16") (pin "6") (pinfunction "1Y_6") (pintype "passive"))
      (node (ref "U18") (pin "1") (pinfunction "1A_1") (pintype "passive"))
    )
    (net (code "32") (name "Net-(U16B-2Y)") (class "Default")
      (node (ref "U16") (pin "4") (pinfunction "2Y_4") (pintype "passive"))
      (node (ref "U18") (pin "4") (pinfunction "2A_4") (pintype "passive"))
    )
    (net (code "33") (name "Net-(U17B-2B)") (class "Default")
      (node (ref "R23") (pin "1") (pinfunction "1_1") (pintype "passive"))
      (node (ref "U17") (pin "5") (pinfunction "2B_5") (pintype "passive"))
      (node (ref "U5") (pin "4") (pinfunction "OUT_4") (pintype "output"))
    )
    (net (code "34") (name "Net-(U17D-4B)") (class "Default")
      (node (ref "R27") (pin "1") (pinfunction "1_1") (pintype "passive"))
      (node (ref "U17") (pin "13") (pinfunction "4B_13") (pintype "passive"))
      (node (ref "U8") (pin "4") (pinfunction "OUT_4") (pintype "output"))
    )
    (net (code "35") (name "Net-(U18C-3A)") (class "Default")
      (node (ref "U18") (pin "12") (pinfunction "4A_12") (pintype "passive"))
      (node (ref "U18") (pin "9") (pinfunction "3A_9") (pintype "passive"))
      (node (ref "U23") (pin "4") (pinfunction "2Y_4") (pintype "passive"))
    )
    (net (code "36") (name "Net-(U18C-3B)") (class "Default")
      (node (ref "U18") (pin "10") (pinfunction "3B_10") (pintype "passive"))
      (node (ref "U20") (pin "8") (pinfunction "Y_8") (pintype "passive"))
    )
    (net (code "37") (name "Net-(U18D-4B)") (class "Default")
      (node (ref "U18") (pin "13") (pinfunction "4B_13") (pintype "passive"))
      (node (ref "U23") (pin "6") (pinfunction "1Y_6") (pintype "passive"))
    )
    (net (code "38") (name "Net-(U19A-Y)") (class "Default")
      (node (ref "U19") (pin "3") (pinfunction "Y_3") (pintype "passive"))
      (node (ref "U22") (pin "12") (pinfunction "S3_12") (pintype "passive"))
    )
    (net (code "39") (name "Net-(U19B-Y)") (class "Default")
      (node (ref "U19") (pin "6") (pinfunction "Y_6") (pintype "passive"))
      (node (ref "U22") (pin "6") (pinfunction "S2_6") (pintype "passive"))
    )
    (net (code "40") (name "Net-(U19C-Y)") (class "Default")
      (node (ref "U19") (pin "8") (pinfunction "Y_8") (pintype "passive"))
      (node (ref "U22") (pin "4") (pinfunction "S1_4") (pintype "passive"))
    )
    (net (code "41") (name "Net-(U19D-Y)") (class "Default")
      (node (ref "U19") (pin "11") (pinfunction "Y_11") (pintype "passive"))
      (node (ref "U20") (pin "1") (pinfunction "A_1") (pintype "passive"))
    )
    (net (code "42") (name "Net-(U20A-B)") (class "Default")
      (node (ref "U20") (pin "2") (pinfunction "B_2") (pintype "passive"))
      (node (ref "U22") (pin "2") (pinfunction "Q1_2") (pintype "passive"))
    )
    (net (code "43") (name "Net-(U20A-C)") (class "Default")
      (node (ref "U20") (pin "4") (pinfunction "C_4") (pintype "passive"))
      (node (ref "U22") (pin "9") (pinfunction "Q2_9") (pintype "passive"))
    )
    (net (code "44") (name "Net-(U20A-D)") (class "Default")
      (node (ref "U20") (pin "5") (pinfunction "D_5") (pintype "passive"))
      (node (ref "U22") (pin "10") (pinfunction "Q3_10") (pintype "passive"))
    )
    (net (code "45") (name "Net-(U20A-Y)") (class "Default")
      (node (ref "U20") (pin "6") (pinfunction "Y_6") (pintype "passive"))
      (node (ref "U23") (pin "3") (pinfunction "2А_3") (pintype "passive"))
    )
    (net (code "46") (name "Net-(U20B-A)") (class "Default")
      (node (ref "R32") (pin "1") (pinfunction "1_1") (pintype "passive"))
      (node (ref "U20") (pin "9") (pinfunction "A_9") (pintype "passive"))
    )
    (net (code "47") (name "Net-(U21A-Y)") (class "Default")
      (node (ref "U21") (pin "1") (pinfunction "Y_1") (pintype "passive"))
      (node (ref "U23") (pin "1") (pinfunction "1A_1") (pintype "passive"))
    )
    (net (code "48") (name "Net-(U21B-A)") (class "Default")
      (node (ref "R35") (pin "2") (pinfunction "2_2") (pintype "passive"))
      (node (ref "U21") (pin "10") (pinfunction "B_10") (pintype "passive"))
      (node (ref "U21") (pin "11") (pinfunction "C_11") (pintype "passive"))
      (node (ref "U21") (pin "12") (pinfunction "D_12") (pintype "passive"))
      (node (ref "U21") (pin "9") (pinfunction "A_9") (pintype "passive"))
    )
    (net (code "49") (name "Net-(U21B-Y)") (class "Default")
      (node (ref "R36") (pin "1") (pinfunction "1_1") (pintype "passive"))
      (node (ref "U21") (pin "13") (pinfunction "Y_13") (pintype "passive"))
    )
    (net (code "50") (name "Net-(U22-OE)") (class "Default")
      (node (ref "R34") (pin "2") (pinfunction "2_2") (pintype "passive"))
      (node (ref "U22") (pin "5") (pinfunction "OE_5") (pintype "passive"))
    )
    (net (code "51") (name "Net-(U22-Q4)") (class "Default")
      (node (ref "R48") (pin "1") (pinfunction "1_1") (pintype "passive"))
      (node (ref "U22") (pin "1") (pinfunction "Q4_1") (pintype "passive"))
    )
    (net (code "52") (name "Net-(U22-S4)") (class "Default")
      (node (ref "R33") (pin "1") (pinfunction "1_1") (pintype "passive"))
      (node (ref "U22") (pin "14") (pinfunction "S4_14") (pintype "passive"))
    )
    (net (code "53") (name "Net-(U24A-in)") (class "Default")
      (node (ref "C11") (pin "2") (pinfunction "2_2") (pintype "passive"))
      (node (ref "R43") (pin "2") (pinfunction "2_2") (pintype "passive"))
      (node (ref "R44") (pin "1") (pinfunction "1_1") (pintype "passive"))
      (node (ref "U24") (pin "2") (pinfunction "in_2") (pintype "passive"))
    )
  )
)
